# LKS_EVB_MCU074DO_V2_0.net
KiCad netlist of a schematic drawn in Altium Designer
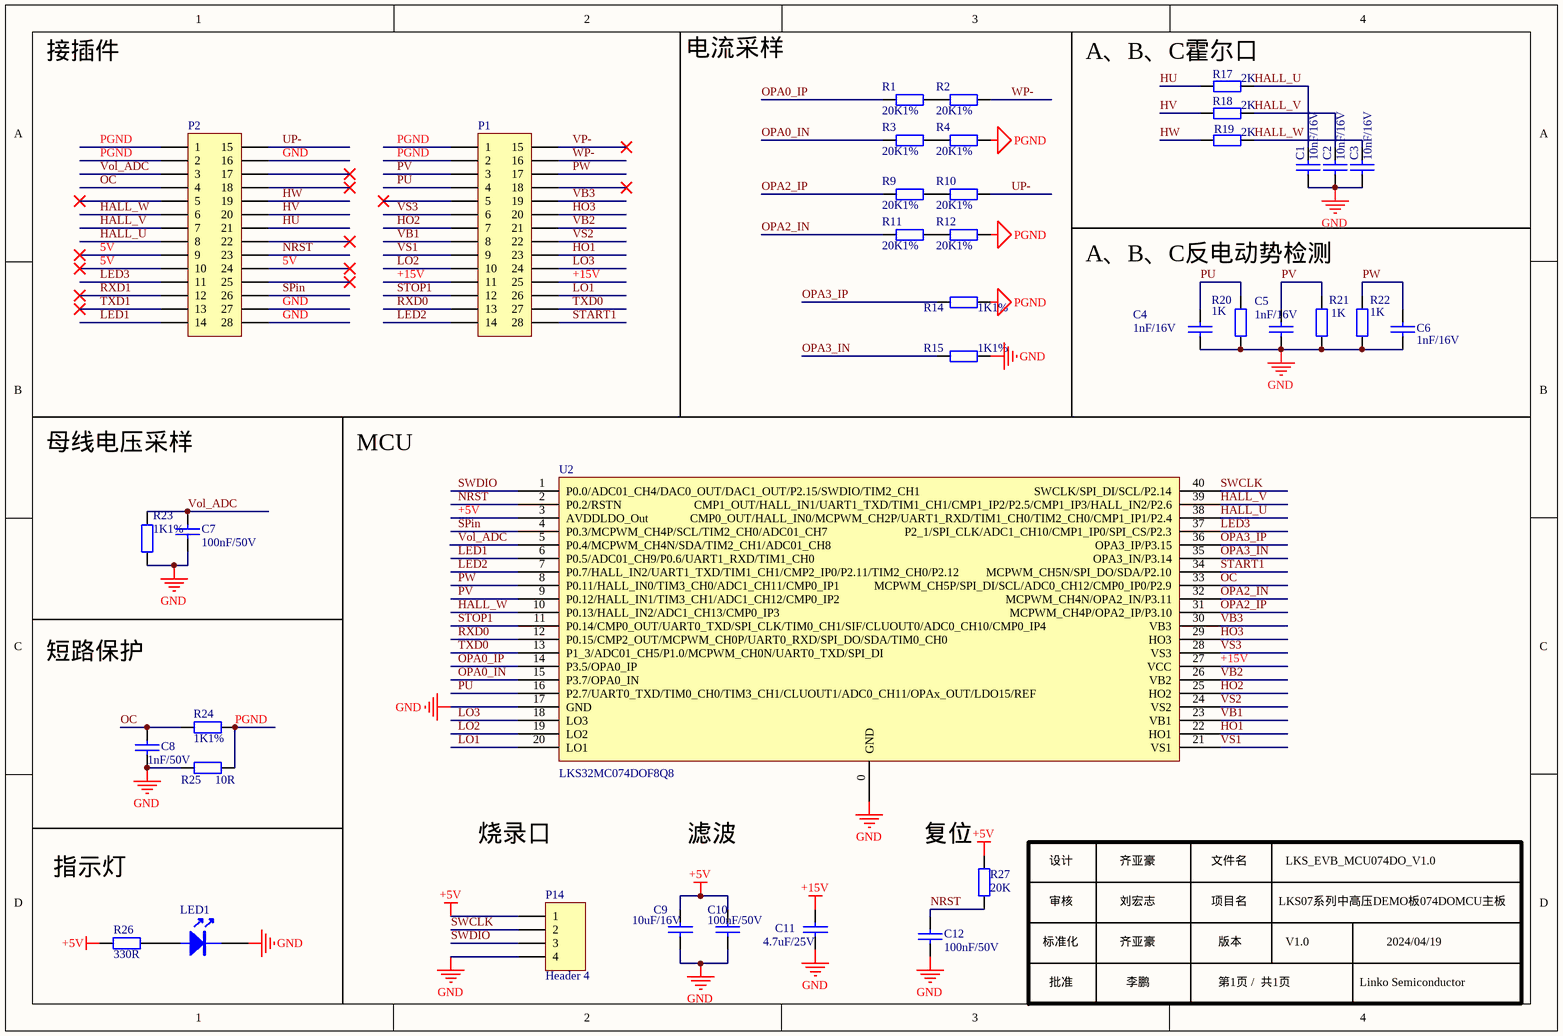
[diagram p0: LKS_EVB_MCU074DO_V2.0.SchDoc]

(export (version "E")
  (design (tool "Eeschema 10.0.6"))
  (components
    (comp (ref "C1")
      (value "10nF/16V")
      (footprint "0603C")
      (description "Capacitor")
      (libsource (lib "*") (part "CAP"))
    )
    (comp (ref "C2")
      (value "10nF/16V")
      (footprint "0603C")
      (description "Capacitor")
      (libsource (lib "*") (part "CAP"))
    )
    (comp (ref "C3")
      (value "10nF/16V")
      (footprint "0603C")
      (description "Capacitor")
      (libsource (lib "*") (part "CAP"))
    )
    (comp (ref "C4")
      (value "1nF/16V")
      (footprint "0603C")
      (description "Capacitor")
      (libsource (lib "*") (part "CAP"))
    )
    (comp (ref "C5")
      (value "1nF/16V")
      (footprint "0603C")
      (description "Capacitor")
      (libsource (lib "*") (part "CAP"))
    )
    (comp (ref "C6")
      (value "1nF/16V")
      (footprint "0603C")
      (description "Capacitor")
      (libsource (lib "*") (part "CAP"))
    )
    (comp (ref "C7")
      (value "100nF/50V")
      (footprint "0603C")
      (description "Capacitor")
      (libsource (lib "*") (part "C"))
    )
    (comp (ref "C8")
      (value "1nF/50V")
      (footprint "0603C")
      (description "Capacitor")
      (libsource (lib "*") (part "C"))
    )
    (comp (ref "C9")
      (value "10uF/16V")
      (footprint "0603C")
      (description "Capacitor")
      (libsource (lib "*") (part "C"))
    )
    (comp (ref "C10")
      (value "100nF/50V")
      (footprint "0603C")
      (description "Capacitor")
      (libsource (lib "*") (part "C"))
    )
    (comp (ref "C11")
      (value "4.7uF/25V")
      (footprint "0603C")
      (description "Capacitor")
      (libsource (lib "*") (part "C"))
    )
    (comp (ref "C12")
      (value "100nF/50V")
      (footprint "0603C")
      (description "Capacitor")
      (libsource (lib "*") (part "C"))
    )
    (comp (ref "LED1")
      (value "LED")
      (footprint "LED 0603R")
      (description "LED_Light")
      (libsource (lib "LINKO_V1.0") (part "LED"))
    )
    (comp (ref "P1")
      (value "Header 14X2A")
      (footprint "HDR 2X14 底层")
      (description "Header, 14-Pin, Dual row")
      (fields (field (name "PUBLISHER") "Altium Limited"))
      (libsource (lib "Miscellaneous Connectors") (part "Header 14X2A"))
    )
    (comp (ref "P2")
      (value "Header 14X2A")
      (footprint "HDR 2X14 底层")
      (description "Header, 14-Pin, Dual row")
      (fields (field (name "PUBLISHER") "Altium Limited"))
      (libsource (lib "Miscellaneous Connectors") (part "Header 14X2A"))
    )
    (comp (ref "P14")
      (value "Header 4")
      (footprint "HDR1X4")
      (description "Header, 4-Pin")
      (fields (field (name "PUBLISHER") "Altium Limited"))
      (libsource (lib "Miscellaneous Connectors") (part "Header 4"))
    )
    (comp (ref "R1")
      (value "20K1%")
      (footprint "0603R")
      (description "Resistor")
      (fields (field (name "PUBLISHER") "Altium Limited"))
      (libsource (lib "LINKO_V1.0") (part "Res"))
    )
    (comp (ref "R2")
      (value "20K1%")
      (footprint "0603R")
      (description "Resistor")
      (fields (field (name "PUBLISHER") "Altium Limited"))
      (libsource (lib "LINKO_V1.0") (part "Res"))
    )
    (comp (ref "R3")
      (value "20K1%")
      (footprint "0603R")
      (description "Resistor")
      (fields (field (name "PUBLISHER") "Altium Limited"))
      (libsource (lib "LINKO_V1.0") (part "Res"))
    )
    (comp (ref "R4")
      (value "20K1%")
      (footprint "0603R")
      (description "Resistor")
      (fields (field (name "PUBLISHER") "Altium Limited"))
      (libsource (lib "LINKO_V1.0") (part "Res"))
    )
    (comp (ref "R9")
      (value "20K1%")
      (footprint "0603R")
      (description "Resistor")
      (fields (field (name "PUBLISHER") "Altium Limited"))
      (libsource (lib "LINKO_V1.0") (part "Res"))
    )
    (comp (ref "R10")
      (value "20K1%")
      (footprint "0603R")
      (description "Resistor")
      (fields (field (name "PUBLISHER") "Altium Limited"))
      (libsource (lib "LINKO_V1.0") (part "Res"))
    )
    (comp (ref "R11")
      (value "20K1%")
      (footprint "0603R")
      (description "Resistor")
      (fields (field (name "PUBLISHER") "Altium Limited"))
      (libsource (lib "LINKO_V1.0") (part "Res"))
    )
    (comp (ref "R12")
      (value "20K1%")
      (footprint "0603R")
      (description "Resistor")
      (fields (field (name "PUBLISHER") "Altium Limited"))
      (libsource (lib "LINKO_V1.0") (part "Res"))
    )
    (comp (ref "R14")
      (value "1K1%")
      (footprint "0603R")
      (description "Resistor")
      (fields (field (name "PUBLISHER") "Altium Limited"))
      (libsource (lib "LINKO_V1.0") (part "Res"))
    )
    (comp (ref "R15")
      (value "1K1%")
      (footprint "0603R")
      (description "Resistor")
      (fields (field (name "PUBLISHER") "Altium Limited"))
      (libsource (lib "LINKO_V1.0") (part "Res"))
    )
    (comp (ref "R17")
      (value "2K")
      (footprint "0603R")
      (description "Resistor")
      (fields (field (name "PUBLISHER") "Altium Limited"))
      (libsource (lib "") (part "Res_1"))
    )
    (comp (ref "R18")
      (value "2K")
      (footprint "0603R")
      (description "Resistor")
      (fields (field (name "PUBLISHER") "Altium Limited"))
      (libsource (lib "") (part "Res_1"))
    )
    (comp (ref "R19")
      (value "2K")
      (footprint "0603R")
      (description "Resistor")
      (fields (field (name "PUBLISHER") "Altium Limited"))
      (libsource (lib "") (part "Res_1"))
    )
    (comp (ref "R20")
      (value "1K")
      (footprint "0603R")
      (description "Resistor")
      (fields (field (name "PUBLISHER") "Altium Limited"))
      (libsource (lib "LINKO_V1.0") (part "Res"))
    )
    (comp (ref "R21")
      (value "1K")
      (footprint "0603R")
      (description "Resistor")
      (fields (field (name "PUBLISHER") "Altium Limited"))
      (libsource (lib "LINKO_V1.0") (part "Res"))
    )
    (comp (ref "R22")
      (value "1K")
      (footprint "0603R")
      (description "Resistor")
      (fields (field (name "PUBLISHER") "Altium Limited"))
      (libsource (lib "LINKO_V1.0") (part "Res"))
    )
    (comp (ref "R23")
      (value "1K1%")
      (footprint "0603R")
      (description "Resistor")
      (fields (field (name "PUBLISHER") "Altium Limited"))
      (libsource (lib "") (part "Res_2"))
    )
    (comp (ref "R24")
      (value "1K1%")
      (footprint "0603R")
      (description "Resistor")
      (fields (field (name "PUBLISHER") "Altium Limited"))
      (libsource (lib "") (part "Res_1"))
    )
    (comp (ref "R25")
      (value "10R")
      (footprint "0603R")
      (description "Resistor")
      (fields (field (name "PUBLISHER") "Altium Limited"))
      (libsource (lib "LINKO_V1.0") (part "Res"))
    )
    (comp (ref "R26")
      (value "330R")
      (footprint "0603R")
      (description "Resistor")
      (fields (field (name "PUBLISHER") "Altium Limited"))
      (libsource (lib "LINKO_V1.0") (part "Res"))
    )
    (comp (ref "R27")
      (value "20K")
      (footprint "0603R")
      (description "Resistor")
      (fields (field (name "PUBLISHER") "Altium Limited"))
      (libsource (lib "") (part "Res_2"))
    )
    (comp (ref "U2")
      (value "LKS32MC074DOF8Q8")
      (footprint "QFN40")
      (description "凌鸥创芯，芯片，96M，64kK-Flash，12K-RAM,Built-in 6N Gate Drive+ldo5v")
      (libsource (lib "LINKO_V1.1") (part "LKS32MC074DOF8Q8"))
    )
  )
  (nets
    (net (code "1") (name "+5V") (class "Default")
      (node (ref "C10") (pin "2") (pinfunction "2_2") (pintype "passive"))
      (node (ref "C9") (pin "2") (pinfunction "2_2") (pintype "passive"))
      (node (ref "P14") (pin "1") (pinfunction "1_1") (pintype "passive"))
      (node (ref "R26") (pin "2") (pinfunction "2_2") (pintype "passive"))
      (node (ref "R27") (pin "2") (pinfunction "2_2") (pintype "passive"))
      (node (ref "U2") (pin "3") (pinfunction "AVDDLDO_Out_3") (pintype "passive"))
    )
    (net (code "2") (name "+15V") (class "Default")
      (node (ref "C11") (pin "2") (pinfunction "2_2") (pintype "passive"))
      (node (ref "P1") (pin "11") (pinfunction "11_11") (pintype "passive"))
      (node (ref "P1") (pin "25") (pinfunction "25_25") (pintype "passive"))
      (node (ref "U2") (pin "27") (pinfunction "VCC_27") (pintype "passive"))
    )
    (net (code "3") (name "/5V") (class "Default")
      (node (ref "P2") (pin "10") (pinfunction "10_10") (pintype "passive"))
      (node (ref "P2") (pin "24") (pinfunction "24_24") (pintype "passive"))
      (node (ref "P2") (pin "9") (pinfunction "9_9") (pintype "passive"))
    )
    (net (code "6") (name "/HALL_U") (class "Default")
      (node (ref "C1") (pin "1") (pinfunction "1_1") (pintype "passive"))
      (node (ref "P2") (pin "8") (pinfunction "8_8") (pintype "passive"))
      (node (ref "R17") (pin "2") (pinfunction "2_2") (pintype "passive"))
      (node (ref "U2") (pin "38") (pinfunction "CMP0_OUT/HALL_IN0/MCPWM_CH2P/UART1_RXD/TIM1_CH0/TIM2_CH0/CMP1_IP1/P2.4_38") (pintype "passive"))
    )
    (net (code "7") (name "/HALL_V") (class "Default")
      (node (ref "C2") (pin "1") (pinfunction "1_1") (pintype "passive"))
      (node (ref "P2") (pin "7") (pinfunction "7_7") (pintype "passive"))
      (node (ref "R18") (pin "2") (pinfunction "2_2") (pintype "passive"))
      (node (ref "U2") (pin "39") (pinfunction "CMP1_OUT/HALL_IN1/UART1_TXD/TIM1_CH1/CMP1_IP2/P2.5/CMP1_IP3/HALL_IN2/P2.6_39") (pintype "passive"))
    )
    (net (code "8") (name "/HALL_W") (class "Default")
      (node (ref "C3") (pin "1") (pinfunction "1_1") (pintype "passive"))
      (node (ref "P2") (pin "6") (pinfunction "6_6") (pintype "passive"))
      (node (ref "R19") (pin "2") (pinfunction "2_2") (pintype "passive"))
      (node (ref "U2") (pin "10") (pinfunction "P0.13/HALL_IN2/ADC1_CH13/CMP0_IP3_10") (pintype "passive"))
    )
    (net (code "9") (name "/HO1") (class "Default")
      (node (ref "P1") (pin "23") (pinfunction "23_23") (pintype "passive"))
      (node (ref "U2") (pin "22") (pinfunction "HO1_22") (pintype "passive"))
    )
    (net (code "10") (name "/HO2") (class "Default")
      (node (ref "P1") (pin "7") (pinfunction "7_7") (pintype "passive"))
      (node (ref "U2") (pin "25") (pinfunction "HO2_25") (pintype "passive"))
    )
    (net (code "11") (name "/HO3") (class "Default")
      (node (ref "P1") (pin "20") (pinfunction "20_20") (pintype "passive"))
      (node (ref "U2") (pin "29") (pinfunction "HO3_29") (pintype "passive"))
    )
    (net (code "12") (name "/HU") (class "Default")
      (node (ref "P2") (pin "21") (pinfunction "21_21") (pintype "passive"))
      (node (ref "R17") (pin "1") (pinfunction "1_1") (pintype "passive"))
    )
    (net (code "13") (name "/HV") (class "Default")
      (node (ref "P2") (pin "20") (pinfunction "20_20") (pintype "passive"))
      (node (ref "R18") (pin "1") (pinfunction "1_1") (pintype "passive"))
    )
    (net (code "14") (name "/HW") (class "Default")
      (node (ref "P2") (pin "19") (pinfunction "19_19") (pintype "passive"))
      (node (ref "R19") (pin "1") (pinfunction "1_1") (pintype "passive"))
    )
    (net (code "15") (name "/LED1") (class "Default")
      (node (ref "P2") (pin "14") (pinfunction "14_14") (pintype "passive"))
      (node (ref "U2") (pin "6") (pinfunction "P0.5/ADC01_CH9/P0.6/UART1_RXD/TIM1_CH0_6") (pintype "passive"))
    )
    (net (code "16") (name "/LED2") (class "Default")
      (node (ref "P1") (pin "14") (pinfunction "14_14") (pintype "passive"))
      (node (ref "U2") (pin "7") (pinfunction "P0.7/HALL_IN2/UART1_TXD/TIM1_CH1/CMP2_IP0/P2.11/TIM2_CH0/P2.12_7") (pintype "passive"))
    )
    (net (code "17") (name "/LED3") (class "Default")
      (node (ref "P2") (pin "11") (pinfunction "11_11") (pintype "passive"))
      (node (ref "U2") (pin "37") (pinfunction "P2_1/SPI_CLK/ADC1_CH10/CMP1_IP0/SPI_CS/P2.3_37") (pintype "passive"))
    )
    (net (code "18") (name "/LO1") (class "Default")
      (node (ref "P1") (pin "26") (pinfunction "26_26") (pintype "passive"))
      (node (ref "U2") (pin "20") (pinfunction "LO1_20") (pintype "passive"))
    )
    (net (code "19") (name "/LO2") (class "Default")
      (node (ref "P1") (pin "10") (pinfunction "10_10") (pintype "passive"))
      (node (ref "U2") (pin "19") (pinfunction "LO2_19") (pintype "passive"))
    )
    (net (code "20") (name "/LO3") (class "Default")
      (node (ref "P1") (pin "24") (pinfunction "24_24") (pintype "passive"))
      (node (ref "U2") (pin "18") (pinfunction "LO3_18") (pintype "passive"))
    )
    (net (code "22") (name "/NRST") (class "Default")
      (node (ref "C12") (pin "1") (pinfunction "1_1") (pintype "passive"))
      (node (ref "P2") (pin "23") (pinfunction "23_23") (pintype "passive"))
      (node (ref "R27") (pin "1") (pinfunction "1_1") (pintype "passive"))
      (node (ref "U2") (pin "2") (pinfunction "P0.2/RSTN_2") (pintype "passive"))
    )
    (net (code "23") (name "/OC") (class "Default")
      (node (ref "C8") (pin "2") (pinfunction "2_2") (pintype "passive"))
      (node (ref "P2") (pin "4") (pinfunction "4_4") (pintype "passive"))
      (node (ref "R24") (pin "1") (pinfunction "1_1") (pintype "passive"))
      (node (ref "U2") (pin "33") (pinfunction "MCPWM_CH5P/SPI_DI/SCL/ADC0_CH12/CMP0_IP0/P2.9_33") (pintype "passive"))
    )
    (net (code "24") (name "/OPA0_IN") (class "Default")
      (node (ref "R3") (pin "2") (pinfunction "2_2") (pintype "passive"))
      (node (ref "U2") (pin "15") (pinfunction "P3.7/OPA0_IN_15") (pintype "passive"))
    )
    (net (code "25") (name "/OPA0_IP") (class "Default")
      (node (ref "R1") (pin "2") (pinfunction "2_2") (pintype "passive"))
      (node (ref "U2") (pin "14") (pinfunction "P3.5/OPA0_IP_14") (pintype "passive"))
    )
    (net (code "26") (name "/OPA2_IN") (class "Default")
      (node (ref "R11") (pin "2") (pinfunction "2_2") (pintype "passive"))
      (node (ref "U2") (pin "32") (pinfunction "MCPWM_CH4N/OPA2_IN/P3.11_32") (pintype "passive"))
    )
    (net (code "27") (name "/OPA2_IP") (class "Default")
      (node (ref "R9") (pin "2") (pinfunction "2_2") (pintype "passive"))
      (node (ref "U2") (pin "31") (pinfunction "MCPWM_CH4P/OPA2_IP/P3.10_31") (pintype "passive"))
    )
    (net (code "28") (name "/OPA3_IN") (class "Default")
      (node (ref "R15") (pin "2") (pinfunction "2_2") (pintype "passive"))
      (node (ref "U2") (pin "35") (pinfunction "OPA3_IN/P3.14_35") (pintype "passive"))
    )
    (net (code "29") (name "/OPA3_IP") (class "Default")
      (node (ref "R14") (pin "2") (pinfunction "2_2") (pintype "passive"))
      (node (ref "U2") (pin "36") (pinfunction "OPA3_IP/P3.15_36") (pintype "passive"))
    )
    (net (code "30") (name "/PU") (class "Default")
      (node (ref "C4") (pin "1") (pinfunction "1_1") (pintype "passive"))
      (node (ref "P1") (pin "4") (pinfunction "4_4") (pintype "passive"))
      (node (ref "R20") (pin "1") (pinfunction "1_1") (pintype "passive"))
      (node (ref "U2") (pin "16") (pinfunction "P2.7/UART0_TXD/TIM0_CH0/TIM3_CH1/CLUOUT1/ADC0_CH11/OPAx_OUT/LDO15/REF_16") (pintype "passive"))
    )
    (net (code "31") (name "/PV") (class "Default")
      (node (ref "C5") (pin "1") (pinfunction "1_1") (pintype "passive"))
      (node (ref "P1") (pin "3") (pinfunction "3_3") (pintype "passive"))
      (node (ref "R21") (pin "1") (pinfunction "1_1") (pintype "passive"))
      (node (ref "U2") (pin "9") (pinfunction "P0.12/HALL_IN1/TIM3_CH1/ADC1_CH12/CMP0_IP2_9") (pintype "passive"))
    )
    (net (code "32") (name "/PW") (class "Default")
      (node (ref "C6") (pin "1") (pinfunction "1_1") (pintype "passive"))
      (node (ref "P1") (pin "17") (pinfunction "17_17") (pintype "passive"))
      (node (ref "R22") (pin "1") (pinfunction "1_1") (pintype "passive"))
      (node (ref "U2") (pin "8") (pinfunction "P0.11/HALL_IN0/TIM3_CH0/ADC1_CH11/CMP0_IP1_8") (pintype "passive"))
    )
    (net (code "33") (name "/RXD0") (class "Default")
      (node (ref "P1") (pin "13") (pinfunction "13_13") (pintype "passive"))
      (node (ref "U2") (pin "12") (pinfunction "P0.15/CMP2_OUT/MCPWM_CH0P/UART0_RXD/SPI_DO/SDA/TIM0_CH0_12") (pintype "passive"))
    )
    (net (code "34") (name "/RXD1") (class "Default")
      (node (ref "P2") (pin "12") (pinfunction "12_12") (pintype "passive+no_connect"))
    )
    (net (code "35") (name "/SPin") (class "Default")
      (node (ref "P2") (pin "26") (pinfunction "26_26") (pintype "passive"))
      (node (ref "U2") (pin "4") (pinfunction "P0.3/MCPWM_CH4P/SCL/TIM2_CH0/ADC01_CH7_4") (pintype "passive"))
    )
    (net (code "36") (name "/START1") (class "Default")
      (node (ref "P1") (pin "28") (pinfunction "28_28") (pintype "passive"))
      (node (ref "U2") (pin "34") (pinfunction "MCPWM_CH5N/SPI_DO/SDA/P2.10_34") (pintype "passive"))
    )
    (net (code "37") (name "/STOP1") (class "Default")
      (node (ref "P1") (pin "12") (pinfunction "12_12") (pintype "passive"))
      (node (ref "U2") (pin "11") (pinfunction "P0.14/CMP0_OUT/UART0_TXD/SPI_CLK/TIM0_CH1/SIF/CLUOUT0/ADC0_CH10/CMP0_IP4_11") (pintype "passive"))
    )
    (net (code "38") (name "/SWCLK") (class "Default")
      (node (ref "P14") (pin "2") (pinfunction "2_2") (pintype "passive"))
      (node (ref "U2") (pin "40") (pinfunction "SWCLK/SPI_DI/SCL/P2.14_40") (pintype "passive"))
    )
    (net (code "39") (name "/SWDIO") (class "Default")
      (node (ref "P14") (pin "3") (pinfunction "3_3") (pintype "passive"))
      (node (ref "U2") (pin "1") (pinfunction "P0.0/ADC01_CH4/DAC0_OUT/DAC1_OUT/P2.15/SWDIO/TIM2_CH1_1") (pintype "passive"))
    )
    (net (code "40") (name "/TXD0") (class "Default")
      (node (ref "P1") (pin "27") (pinfunction "27_27") (pintype "passive"))
      (node (ref "U2") (pin "13") (pinfunction "P1_3/ADC01_CH5/P1.0/MCPWM_CH0N/UART0_TXD/SPI_DI_13") (pintype "passive"))
    )
    (net (code "41") (name "/TXD1") (class "Default")
      (node (ref "P2") (pin "13") (pinfunction "13_13") (pintype "passive+no_connect"))
    )
    (net (code "42") (name "/UP-") (class "Default")
      (node (ref "P2") (pin "15") (pinfunction "15_15") (pintype "passive"))
      (node (ref "R10") (pin "1") (pinfunction "1_1") (pintype "passive"))
    )
    (net (code "43") (name "/VB1") (class "Default")
      (node (ref "P1") (pin "8") (pinfunction "8_8") (pintype "passive"))
      (node (ref "U2") (pin "23") (pinfunction "VB1_23") (pintype "passive"))
    )
    (net (code "44") (name "/VB2") (class "Default")
      (node (ref "P1") (pin "21") (pinfunction "21_21") (pintype "passive"))
      (node (ref "U2") (pin "26") (pinfunction "VB2_26") (pintype "passive"))
    )
    (net (code "45") (name "/VB3") (class "Default")
      (node (ref "P1") (pin "19") (pinfunction "19_19") (pintype "passive"))
      (node (ref "U2") (pin "30") (pinfunction "VB3_30") (pintype "passive"))
    )
    (net (code "46") (name "/VP-") (class "Default")
      (node (ref "P1") (pin "15") (pinfunction "15_15") (pintype "passive+no_connect"))
    )
    (net (code "47") (name "/VS1") (class "Default")
      (node (ref "P1") (pin "9") (pinfunction "9_9") (pintype "passive"))
      (node (ref "U2") (pin "21") (pinfunction "VS1_21") (pintype "passive"))
    )
    (net (code "48") (name "/VS2") (class "Default")
      (node (ref "P1") (pin "22") (pinfunction "22_22") (pintype "passive"))
      (node (ref "U2") (pin "24") (pinfunction "VS2_24") (pintype "passive"))
    )
    (net (code "49") (name "/VS3") (class "Default")
      (node (ref "P1") (pin "6") (pinfunction "6_6") (pintype "passive"))
      (node (ref "U2") (pin "28") (pinfunction "VS3_28") (pintype "passive"))
    )
    (net (code "50") (name "/Vol_ADC") (class "Default")
      (node (ref "C7") (pin "2") (pinfunction "2_2") (pintype "passive"))
      (node (ref "P2") (pin "3") (pinfunction "3_3") (pintype "passive"))
      (node (ref "R23") (pin "2") (pinfunction "2_2") (pintype "passive"))
      (node (ref "U2") (pin "5") (pinfunction "P0.4/MCPWM_CH4N/SDA/TIM2_CH1/ADC01_CH8_5") (pintype "passive"))
    )
    (net (code "51") (name "/WP-") (class "Default")
      (node (ref "P1") (pin "16") (pinfunction "16_16") (pintype "passive"))
      (node (ref "R2") (pin "1") (pinfunction "1_1") (pintype "passive"))
    )
    (net (code "53") (name "GND") (class "Default")
      (node (ref "C1") (pin "2") (pinfunction "2_2") (pintype "passive"))
      (node (ref "C10") (pin "1") (pinfunction "1_1") (pintype "passive"))
      (node (ref "C11") (pin "1") (pinfunction "1_1") (pintype "passive"))
      (node (ref "C12") (pin "2") (pinfunction "2_2") (pintype "passive"))
      (node (ref "C2") (pin "2") (pinfunction "2_2") (pintype "passive"))
      (node (ref "C3") (pin "2") (pinfunction "2_2") (pintype "passive"))
      (node (ref "C4") (pin "2") (pinfunction "2_2") (pintype "passive"))
      (node (ref "C5") (pin "2") (pinfunction "2_2") (pintype "passive"))
      (node (ref "C6") (pin "2") (pinfunction "2_2") (pintype "passive"))
      (node (ref "C7") (pin "1") (pinfunction "1_1") (pintype "passive"))
      (node (ref "C8") (pin "1") (pinfunction "1_1") (pintype "passive"))
      (node (ref "C9") (pin "1") (pinfunction "1_1") (pintype "passive"))
      (node (ref "LED1") (pin "2") (pinfunction "K_2") (pintype "passive"))
      (node (ref "P14") (pin "4") (pinfunction "4_4") (pintype "passive"))
      (node (ref "P2") (pin "16") (pinfunction "16_16") (pintype "passive"))
      (node (ref "P2") (pin "27") (pinfunction "27_27") (pintype "passive"))
      (node (ref "P2") (pin "28") (pinfunction "28_28") (pintype "passive"))
      (node (ref "R15") (pin "1") (pinfunction "1_1") (pintype "passive"))
      (node (ref "R20") (pin "2") (pinfunction "2_2") (pintype "passive"))
      (node (ref "R21") (pin "2") (pinfunction "2_2") (pintype "passive"))
      (node (ref "R22") (pin "2") (pinfunction "2_2") (pintype "passive"))
      (node (ref "R23") (pin "1") (pinfunction "1_1") (pintype "passive"))
      (node (ref "R25") (pin "2") (pinfunction "2_2") (pintype "passive"))
      (node (ref "U2") (pin "0") (pinfunction "GND_0") (pintype "passive"))
      (node (ref "U2") (pin "17") (pinfunction "GND_17") (pintype "passive"))
    )
    (net (code "54") (name "Net-(LED1-A)") (class "Default")
      (node (ref "LED1") (pin "1") (pinfunction "A_1") (pintype "passive"))
      (node (ref "R26") (pin "1") (pinfunction "1_1") (pintype "passive"))
    )
    (net (code "55") (name "Net-(R1-Pad1)") (class "Default")
      (node (ref "R1") (pin "1") (pinfunction "1_1") (pintype "passive"))
      (node (ref "R2") (pin "2") (pinfunction "2_2") (pintype "passive"))
    )
    (net (code "56") (name "Net-(R3-Pad1)") (class "Default")
      (node (ref "R3") (pin "1") (pinfunction "1_1") (pintype "passive"))
      (node (ref "R4") (pin "2") (pinfunction "2_2") (pintype "passive"))
    )
    (net (code "57") (name "Net-(R10-Pad2)") (class "Default")
      (node (ref "R10") (pin "2") (pinfunction "2_2") (pintype "passive"))
      (node (ref "R9") (pin "1") (pinfunction "1_1") (pintype "passive"))
    )
    (net (code "58") (name "Net-(R11-Pad1)") (class "Default")
      (node (ref "R11") (pin "1") (pinfunction "1_1") (pintype "passive"))
      (node (ref "R12") (pin "2") (pinfunction "2_2") (pintype "passive"))
    )
    (net (code "59") (name "PGND") (class "Default")
      (node (ref "P1") (pin "1") (pinfunction "1_1") (pintype "passive"))
      (node (ref "P1") (pin "2") (pinfunction "2_2") (pintype "passive"))
      (node (ref "P2") (pin "1") (pinfunction "1_1") (pintype "passive"))
      (node (ref "P2") (pin "2") (pinfunction "2_2") (pintype "passive"))
      (node (ref "R12") (pin "1") (pinfunction "1_1") (pintype "passive"))
      (node (ref "R14") (pin "1") (pinfunction "1_1") (pintype "passive"))
      (node (ref "R24") (pin "2") (pinfunction "2_2") (pintype "passive"))
      (node (ref "R25") (pin "1") (pinfunction "1_1") (pintype "passive"))
      (node (ref "R4") (pin "1") (pinfunction "1_1") (pintype "passive"))
    )
    (net (code "60") (name "unconnected-(P1-Pad5)") (class "Default")
      (node (ref "P1") (pin "5") (pinfunction "5_5") (pintype "passive+no_connect"))
    )
    (net (code "61") (name "unconnected-(P1-Pad18)") (class "Default")
      (node (ref "P1") (pin "18") (pinfunction "18_18") (pintype "passive+no_connect"))
    )
    (net (code "62") (name "unconnected-(P2-Pad5)") (class "Default")
      (node (ref "P2") (pin "5") (pinfunction "5_5") (pintype "passive+no_connect"))
    )
    (net (code "63") (name "unconnected-(P2-Pad17)") (class "Default")
      (node (ref "P2") (pin "17") (pinfunction "17_17") (pintype "passive+no_connect"))
    )
    (net (code "64") (name "unconnected-(P2-Pad18)") (class "Default")
      (node (ref "P2") (pin "18") (pinfunction "18_18") (pintype "passive+no_connect"))
    )
    (net (code "65") (name "unconnected-(P2-Pad22)") (class "Default")
      (node (ref "P2") (pin "22") (pinfunction "22_22") (pintype "passive+no_connect"))
    )
    (net (code "66") (name "unconnected-(P2-Pad25)") (class "Default")
      (node (ref "P2") (pin "25") (pinfunction "25_25") (pintype "passive+no_connect"))
    )
  )
)
